# OSPLC2_2_IO3.net
KiCad netlist of a schematic drawn in Altium Designer
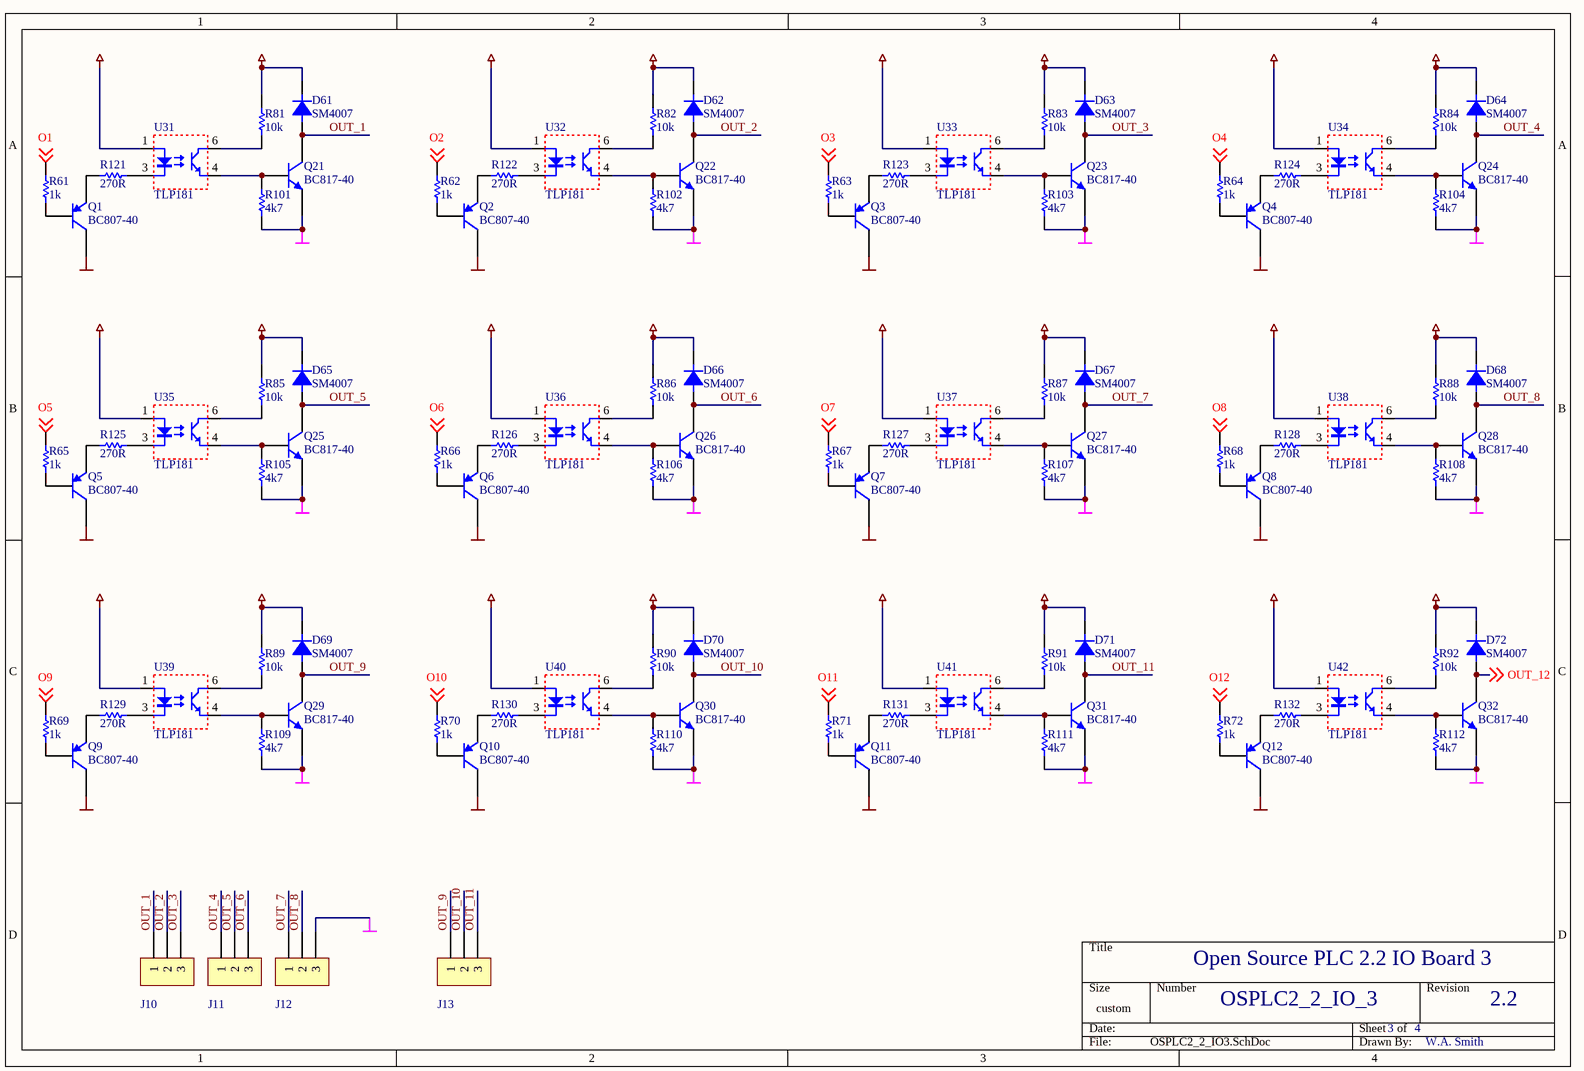
[diagram p0: OSPLC2_2_IO3.SchDoc]

(export (version "E")
  (design (tool "Eeschema 10.0.6"))
  (components
    (comp (ref "D61")
      (value "SM4007")
      (footprint "MELF-2.2x2.5")
      (description "1A, 1000V MELF Rectifier")
      (libsource (lib "ARM_projects") (part "SM4007"))
    )
    (comp (ref "D62")
      (value "SM4007")
      (footprint "MELF-2.2x2.5")
      (description "1A, 1000V MELF Rectifier")
      (libsource (lib "ARM_projects") (part "SM4007"))
    )
    (comp (ref "D63")
      (value "SM4007")
      (footprint "MELF-2.2x2.5")
      (description "1A, 1000V MELF Rectifier")
      (libsource (lib "ARM_projects") (part "SM4007"))
    )
    (comp (ref "D64")
      (value "SM4007")
      (footprint "MELF-2.2x2.5")
      (description "1A, 1000V MELF Rectifier")
      (libsource (lib "ARM_projects") (part "SM4007"))
    )
    (comp (ref "D65")
      (value "SM4007")
      (footprint "MELF-2.2x2.5")
      (description "1A, 1000V MELF Rectifier")
      (libsource (lib "ARM_projects") (part "SM4007"))
    )
    (comp (ref "D66")
      (value "SM4007")
      (footprint "MELF-2.2x2.5")
      (description "1A, 1000V MELF Rectifier")
      (libsource (lib "ARM_projects") (part "SM4007"))
    )
    (comp (ref "D67")
      (value "SM4007")
      (footprint "MELF-2.2x2.5")
      (description "1A, 1000V MELF Rectifier")
      (libsource (lib "ARM_projects") (part "SM4007"))
    )
    (comp (ref "D68")
      (value "SM4007")
      (footprint "MELF-2.2x2.5")
      (description "1A, 1000V MELF Rectifier")
      (libsource (lib "ARM_projects") (part "SM4007"))
    )
    (comp (ref "D69")
      (value "SM4007")
      (footprint "MELF-2.2x2.5")
      (description "1A, 1000V MELF Rectifier")
      (libsource (lib "ARM_projects") (part "SM4007"))
    )
    (comp (ref "D70")
      (value "SM4007")
      (footprint "MELF-2.2x2.5")
      (description "1A, 1000V MELF Rectifier")
      (libsource (lib "ARM_projects") (part "SM4007"))
    )
    (comp (ref "D71")
      (value "SM4007")
      (footprint "MELF-2.2x2.5")
      (description "1A, 1000V MELF Rectifier")
      (libsource (lib "ARM_projects") (part "SM4007"))
    )
    (comp (ref "D72")
      (value "SM4007")
      (footprint "MELF-2.2x2.5")
      (description "1A, 1000V MELF Rectifier")
      (libsource (lib "ARM_projects") (part "SM4007"))
    )
    (comp (ref "J10")
      (value "PCB TERMINAL")
      (footprint "TERMINAL_3WAY_5MM")
      (description "5mm spaced PCB terminal, 3 pole")
      (libsource (lib "ARM_projects") (part "TERMINAL_3WAY_5MM"))
    )
    (comp (ref "J11")
      (value "PCB TERMINAL")
      (footprint "TERMINAL_3WAY_5MM")
      (description "5mm spaced PCB terminal, 3 pole")
      (libsource (lib "ARM_projects") (part "TERMINAL_3WAY_5MM"))
    )
    (comp (ref "J12")
      (value "PCB TERMINAL")
      (footprint "TERMINAL_3WAY_5MM")
      (description "5mm spaced PCB terminal, 3 pole")
      (libsource (lib "ARM_projects") (part "TERMINAL_3WAY_5MM"))
    )
    (comp (ref "J13")
      (value "PCB TERMINAL")
      (footprint "TERMINAL_3WAY_5MM")
      (description "5mm spaced PCB terminal, 3 pole")
      (libsource (lib "ARM_projects") (part "TERMINAL_3WAY_5MM"))
    )
    (comp (ref "Q1")
      (value "BC807-40")
      (footprint "SO-G3/Y1")
      (description "PNP General Purpose Amplifier")
      (fields
        (field (name "MANUFACTURER") "Fairchild Semiconductor")
        (field (name "PUBLISHER") "Altium Limited")
      )
      (libsource (lib "FSC Discrete BJT") (part "BC807-40"))
    )
    (comp (ref "Q2")
      (value "BC807-40")
      (footprint "SO-G3/Y1")
      (description "PNP General Purpose Amplifier")
      (fields
        (field (name "MANUFACTURER") "Fairchild Semiconductor")
        (field (name "PUBLISHER") "Altium Limited")
      )
      (libsource (lib "FSC Discrete BJT") (part "BC807-40"))
    )
    (comp (ref "Q3")
      (value "BC807-40")
      (footprint "SO-G3/Y1")
      (description "PNP General Purpose Amplifier")
      (fields
        (field (name "MANUFACTURER") "Fairchild Semiconductor")
        (field (name "PUBLISHER") "Altium Limited")
      )
      (libsource (lib "FSC Discrete BJT") (part "BC807-40"))
    )
    (comp (ref "Q4")
      (value "BC807-40")
      (footprint "SO-G3/Y1")
      (description "PNP General Purpose Amplifier")
      (fields
        (field (name "MANUFACTURER") "Fairchild Semiconductor")
        (field (name "PUBLISHER") "Altium Limited")
      )
      (libsource (lib "FSC Discrete BJT") (part "BC807-40"))
    )
    (comp (ref "Q5")
      (value "BC807-40")
      (footprint "SO-G3/Y1")
      (description "PNP General Purpose Amplifier")
      (fields
        (field (name "MANUFACTURER") "Fairchild Semiconductor")
        (field (name "PUBLISHER") "Altium Limited")
      )
      (libsource (lib "FSC Discrete BJT") (part "BC807-40"))
    )
    (comp (ref "Q6")
      (value "BC807-40")
      (footprint "SO-G3/Y1")
      (description "PNP General Purpose Amplifier")
      (fields
        (field (name "MANUFACTURER") "Fairchild Semiconductor")
        (field (name "PUBLISHER") "Altium Limited")
      )
      (libsource (lib "FSC Discrete BJT") (part "BC807-40"))
    )
    (comp (ref "Q7")
      (value "BC807-40")
      (footprint "SO-G3/Y1")
      (description "PNP General Purpose Amplifier")
      (fields
        (field (name "MANUFACTURER") "Fairchild Semiconductor")
        (field (name "PUBLISHER") "Altium Limited")
      )
      (libsource (lib "FSC Discrete BJT") (part "BC807-40"))
    )
    (comp (ref "Q8")
      (value "BC807-40")
      (footprint "SO-G3/Y1")
      (description "PNP General Purpose Amplifier")
      (fields
        (field (name "MANUFACTURER") "Fairchild Semiconductor")
        (field (name "PUBLISHER") "Altium Limited")
      )
      (libsource (lib "FSC Discrete BJT") (part "BC807-40"))
    )
    (comp (ref "Q9")
      (value "BC807-40")
      (footprint "SO-G3/Y1")
      (description "PNP General Purpose Amplifier")
      (fields
        (field (name "MANUFACTURER") "Fairchild Semiconductor")
        (field (name "PUBLISHER") "Altium Limited")
      )
      (libsource (lib "FSC Discrete BJT") (part "BC807-40"))
    )
    (comp (ref "Q10")
      (value "BC807-40")
      (footprint "SO-G3/Y1")
      (description "PNP General Purpose Amplifier")
      (fields
        (field (name "MANUFACTURER") "Fairchild Semiconductor")
        (field (name "PUBLISHER") "Altium Limited")
      )
      (libsource (lib "FSC Discrete BJT") (part "BC807-40"))
    )
    (comp (ref "Q11")
      (value "BC807-40")
      (footprint "SO-G3/Y1")
      (description "PNP General Purpose Amplifier")
      (fields
        (field (name "MANUFACTURER") "Fairchild Semiconductor")
        (field (name "PUBLISHER") "Altium Limited")
      )
      (libsource (lib "FSC Discrete BJT") (part "BC807-40"))
    )
    (comp (ref "Q12")
      (value "BC807-40")
      (footprint "SO-G3/Y1")
      (description "PNP General Purpose Amplifier")
      (fields
        (field (name "MANUFACTURER") "Fairchild Semiconductor")
        (field (name "PUBLISHER") "Altium Limited")
      )
      (libsource (lib "FSC Discrete BJT") (part "BC807-40"))
    )
    (comp (ref "Q21")
      (value "BC817-40")
      (footprint "SO-G3/Y1")
      (description "NPN General Purpose Amplifier")
      (fields
        (field (name "MANUFACTURER") "Fairchild Semiconductor")
        (field (name "PUBLISHER") "Altium Limited")
      )
      (libsource (lib "FSC Discrete BJT") (part "BC817-40"))
    )
    (comp (ref "Q22")
      (value "BC817-40")
      (footprint "SO-G3/Y1")
      (description "NPN General Purpose Amplifier")
      (fields
        (field (name "MANUFACTURER") "Fairchild Semiconductor")
        (field (name "PUBLISHER") "Altium Limited")
      )
      (libsource (lib "FSC Discrete BJT") (part "BC817-40"))
    )
    (comp (ref "Q23")
      (value "BC817-40")
      (footprint "SO-G3/Y1")
      (description "NPN General Purpose Amplifier")
      (fields
        (field (name "MANUFACTURER") "Fairchild Semiconductor")
        (field (name "PUBLISHER") "Altium Limited")
      )
      (libsource (lib "FSC Discrete BJT") (part "BC817-40"))
    )
    (comp (ref "Q24")
      (value "BC817-40")
      (footprint "SO-G3/Y1")
      (description "NPN General Purpose Amplifier")
      (fields
        (field (name "MANUFACTURER") "Fairchild Semiconductor")
        (field (name "PUBLISHER") "Altium Limited")
      )
      (libsource (lib "FSC Discrete BJT") (part "BC817-40"))
    )
    (comp (ref "Q25")
      (value "BC817-40")
      (footprint "SO-G3/Y1")
      (description "NPN General Purpose Amplifier")
      (fields
        (field (name "MANUFACTURER") "Fairchild Semiconductor")
        (field (name "PUBLISHER") "Altium Limited")
      )
      (libsource (lib "FSC Discrete BJT") (part "BC817-40"))
    )
    (comp (ref "Q26")
      (value "BC817-40")
      (footprint "SO-G3/Y1")
      (description "NPN General Purpose Amplifier")
      (fields
        (field (name "MANUFACTURER") "Fairchild Semiconductor")
        (field (name "PUBLISHER") "Altium Limited")
      )
      (libsource (lib "FSC Discrete BJT") (part "BC817-40"))
    )
    (comp (ref "Q27")
      (value "BC817-40")
      (footprint "SO-G3/Y1")
      (description "NPN General Purpose Amplifier")
      (fields
        (field (name "MANUFACTURER") "Fairchild Semiconductor")
        (field (name "PUBLISHER") "Altium Limited")
      )
      (libsource (lib "FSC Discrete BJT") (part "BC817-40"))
    )
    (comp (ref "Q28")
      (value "BC817-40")
      (footprint "SO-G3/Y1")
      (description "NPN General Purpose Amplifier")
      (fields
        (field (name "MANUFACTURER") "Fairchild Semiconductor")
        (field (name "PUBLISHER") "Altium Limited")
      )
      (libsource (lib "FSC Discrete BJT") (part "BC817-40"))
    )
    (comp (ref "Q29")
      (value "BC817-40")
      (footprint "SO-G3/Y1")
      (description "NPN General Purpose Amplifier")
      (fields
        (field (name "MANUFACTURER") "Fairchild Semiconductor")
        (field (name "PUBLISHER") "Altium Limited")
      )
      (libsource (lib "FSC Discrete BJT") (part "BC817-40"))
    )
    (comp (ref "Q30")
      (value "BC817-40")
      (footprint "SO-G3/Y1")
      (description "NPN General Purpose Amplifier")
      (fields
        (field (name "MANUFACTURER") "Fairchild Semiconductor")
        (field (name "PUBLISHER") "Altium Limited")
      )
      (libsource (lib "FSC Discrete BJT") (part "BC817-40"))
    )
    (comp (ref "Q31")
      (value "BC817-40")
      (footprint "SO-G3/Y1")
      (description "NPN General Purpose Amplifier")
      (fields
        (field (name "MANUFACTURER") "Fairchild Semiconductor")
        (field (name "PUBLISHER") "Altium Limited")
      )
      (libsource (lib "FSC Discrete BJT") (part "BC817-40"))
    )
    (comp (ref "Q32")
      (value "BC817-40")
      (footprint "SO-G3/Y1")
      (description "NPN General Purpose Amplifier")
      (fields
        (field (name "MANUFACTURER") "Fairchild Semiconductor")
        (field (name "PUBLISHER") "Altium Limited")
      )
      (libsource (lib "FSC Discrete BJT") (part "BC817-40"))
    )
    (comp (ref "R61")
      (value "0805")
      (footprint "0805")
      (description "0805 footprint resistor")
      (fields (field (name "ALTIUM_VALUE") "1k"))
      (libsource (lib "Integrated Comp_lib") (part "RES_0805"))
    )
    (comp (ref "R62")
      (value "0805")
      (footprint "0805")
      (description "0805 footprint resistor")
      (fields (field (name "ALTIUM_VALUE") "1k"))
      (libsource (lib "Integrated Comp_lib") (part "RES_0805"))
    )
    (comp (ref "R63")
      (value "0805")
      (footprint "0805")
      (description "0805 footprint resistor")
      (fields (field (name "ALTIUM_VALUE") "1k"))
      (libsource (lib "Integrated Comp_lib") (part "RES_0805"))
    )
    (comp (ref "R64")
      (value "0805")
      (footprint "0805")
      (description "0805 footprint resistor")
      (fields (field (name "ALTIUM_VALUE") "1k"))
      (libsource (lib "Integrated Comp_lib") (part "RES_0805"))
    )
    (comp (ref "R65")
      (value "0805")
      (footprint "0805")
      (description "0805 footprint resistor")
      (fields (field (name "ALTIUM_VALUE") "1k"))
      (libsource (lib "Integrated Comp_lib") (part "RES_0805"))
    )
    (comp (ref "R66")
      (value "0805")
      (footprint "0805")
      (description "0805 footprint resistor")
      (fields (field (name "ALTIUM_VALUE") "1k"))
      (libsource (lib "Integrated Comp_lib") (part "RES_0805"))
    )
    (comp (ref "R67")
      (value "0805")
      (footprint "0805")
      (description "0805 footprint resistor")
      (fields (field (name "ALTIUM_VALUE") "1k"))
      (libsource (lib "Integrated Comp_lib") (part "RES_0805"))
    )
    (comp (ref "R68")
      (value "0805")
      (footprint "0805")
      (description "0805 footprint resistor")
      (fields (field (name "ALTIUM_VALUE") "1k"))
      (libsource (lib "Integrated Comp_lib") (part "RES_0805"))
    )
    (comp (ref "R69")
      (value "0805")
      (footprint "0805")
      (description "0805 footprint resistor")
      (fields (field (name "ALTIUM_VALUE") "1k"))
      (libsource (lib "Integrated Comp_lib") (part "RES_0805"))
    )
    (comp (ref "R70")
      (value "0805")
      (footprint "0805")
      (description "0805 footprint resistor")
      (fields (field (name "ALTIUM_VALUE") "1k"))
      (libsource (lib "Integrated Comp_lib") (part "RES_0805"))
    )
    (comp (ref "R71")
      (value "0805")
      (footprint "0805")
      (description "0805 footprint resistor")
      (fields (field (name "ALTIUM_VALUE") "1k"))
      (libsource (lib "Integrated Comp_lib") (part "RES_0805"))
    )
    (comp (ref "R72")
      (value "0805")
      (footprint "0805")
      (description "0805 footprint resistor")
      (fields (field (name "ALTIUM_VALUE") "1k"))
      (libsource (lib "Integrated Comp_lib") (part "RES_0805"))
    )
    (comp (ref "R81")
      (value "0805")
      (footprint "0805")
      (description "0805 footprint resistor")
      (fields (field (name "ALTIUM_VALUE") "10k"))
      (libsource (lib "Integrated Comp_lib") (part "RES_0805"))
    )
    (comp (ref "R82")
      (value "0805")
      (footprint "0805")
      (description "0805 footprint resistor")
      (fields (field (name "ALTIUM_VALUE") "10k"))
      (libsource (lib "Integrated Comp_lib") (part "RES_0805"))
    )
    (comp (ref "R83")
      (value "0805")
      (footprint "0805")
      (description "0805 footprint resistor")
      (fields (field (name "ALTIUM_VALUE") "10k"))
      (libsource (lib "Integrated Comp_lib") (part "RES_0805"))
    )
    (comp (ref "R84")
      (value "0805")
      (footprint "0805")
      (description "0805 footprint resistor")
      (fields (field (name "ALTIUM_VALUE") "10k"))
      (libsource (lib "Integrated Comp_lib") (part "RES_0805"))
    )
    (comp (ref "R85")
      (value "0805")
      (footprint "0805")
      (description "0805 footprint resistor")
      (fields (field (name "ALTIUM_VALUE") "10k"))
      (libsource (lib "Integrated Comp_lib") (part "RES_0805"))
    )
    (comp (ref "R86")
      (value "0805")
      (footprint "0805")
      (description "0805 footprint resistor")
      (fields (field (name "ALTIUM_VALUE") "10k"))
      (libsource (lib "Integrated Comp_lib") (part "RES_0805"))
    )
    (comp (ref "R87")
      (value "0805")
      (footprint "0805")
      (description "0805 footprint resistor")
      (fields (field (name "ALTIUM_VALUE") "10k"))
      (libsource (lib "Integrated Comp_lib") (part "RES_0805"))
    )
    (comp (ref "R88")
      (value "0805")
      (footprint "0805")
      (description "0805 footprint resistor")
      (fields (field (name "ALTIUM_VALUE") "10k"))
      (libsource (lib "Integrated Comp_lib") (part "RES_0805"))
    )
    (comp (ref "R89")
      (value "0805")
      (footprint "0805")
      (description "0805 footprint resistor")
      (fields (field (name "ALTIUM_VALUE") "10k"))
      (libsource (lib "Integrated Comp_lib") (part "RES_0805"))
    )
    (comp (ref "R90")
      (value "0805")
      (footprint "0805")
      (description "0805 footprint resistor")
      (fields (field (name "ALTIUM_VALUE") "10k"))
      (libsource (lib "Integrated Comp_lib") (part "RES_0805"))
    )
    (comp (ref "R91")
      (value "0805")
      (footprint "0805")
      (description "0805 footprint resistor")
      (fields (field (name "ALTIUM_VALUE") "10k"))
      (libsource (lib "Integrated Comp_lib") (part "RES_0805"))
    )
    (comp (ref "R92")
      (value "0805")
      (footprint "0805")
      (description "0805 footprint resistor")
      (fields (field (name "ALTIUM_VALUE") "10k"))
      (libsource (lib "Integrated Comp_lib") (part "RES_0805"))
    )
    (comp (ref "R101")
      (value "0805")
      (footprint "0805")
      (description "0805 footprint resistor")
      (fields (field (name "ALTIUM_VALUE") "4k7"))
      (libsource (lib "Integrated Comp_lib") (part "RES_0805"))
    )
    (comp (ref "R102")
      (value "0805")
      (footprint "0805")
      (description "0805 footprint resistor")
      (fields (field (name "ALTIUM_VALUE") "4k7"))
      (libsource (lib "Integrated Comp_lib") (part "RES_0805"))
    )
    (comp (ref "R103")
      (value "0805")
      (footprint "0805")
      (description "0805 footprint resistor")
      (fields (field (name "ALTIUM_VALUE") "4k7"))
      (libsource (lib "Integrated Comp_lib") (part "RES_0805"))
    )
    (comp (ref "R104")
      (value "0805")
      (footprint "0805")
      (description "0805 footprint resistor")
      (fields (field (name "ALTIUM_VALUE") "4k7"))
      (libsource (lib "Integrated Comp_lib") (part "RES_0805"))
    )
    (comp (ref "R105")
      (value "0805")
      (footprint "0805")
      (description "0805 footprint resistor")
      (fields (field (name "ALTIUM_VALUE") "4k7"))
      (libsource (lib "Integrated Comp_lib") (part "RES_0805"))
    )
    (comp (ref "R106")
      (value "0805")
      (footprint "0805")
      (description "0805 footprint resistor")
      (fields (field (name "ALTIUM_VALUE") "4k7"))
      (libsource (lib "Integrated Comp_lib") (part "RES_0805"))
    )
    (comp (ref "R107")
      (value "0805")
      (footprint "0805")
      (description "0805 footprint resistor")
      (fields (field (name "ALTIUM_VALUE") "4k7"))
      (libsource (lib "Integrated Comp_lib") (part "RES_0805"))
    )
    (comp (ref "R108")
      (value "0805")
      (footprint "0805")
      (description "0805 footprint resistor")
      (fields (field (name "ALTIUM_VALUE") "4k7"))
      (libsource (lib "Integrated Comp_lib") (part "RES_0805"))
    )
    (comp (ref "R109")
      (value "0805")
      (footprint "0805")
      (description "0805 footprint resistor")
      (fields (field (name "ALTIUM_VALUE") "4k7"))
      (libsource (lib "Integrated Comp_lib") (part "RES_0805"))
    )
    (comp (ref "R110")
      (value "0805")
      (footprint "0805")
      (description "0805 footprint resistor")
      (fields (field (name "ALTIUM_VALUE") "4k7"))
      (libsource (lib "Integrated Comp_lib") (part "RES_0805"))
    )
    (comp (ref "R111")
      (value "0805")
      (footprint "0805")
      (description "0805 footprint resistor")
      (fields (field (name "ALTIUM_VALUE") "4k7"))
      (libsource (lib "Integrated Comp_lib") (part "RES_0805"))
    )
    (comp (ref "R112")
      (value "0805")
      (footprint "0805")
      (description "0805 footprint resistor")
      (fields (field (name "ALTIUM_VALUE") "4k7"))
      (libsource (lib "Integrated Comp_lib") (part "RES_0805"))
    )
    (comp (ref "R121")
      (value "0805")
      (footprint "0805")
      (description "0805 footprint resistor")
      (fields (field (name "ALTIUM_VALUE") "270R"))
      (libsource (lib "Integrated Comp_lib") (part "RES_0805"))
    )
    (comp (ref "R122")
      (value "0805")
      (footprint "0805")
      (description "0805 footprint resistor")
      (fields (field (name "ALTIUM_VALUE") "270R"))
      (libsource (lib "Integrated Comp_lib") (part "RES_0805"))
    )
    (comp (ref "R123")
      (value "0805")
      (footprint "0805")
      (description "0805 footprint resistor")
      (fields (field (name "ALTIUM_VALUE") "270R"))
      (libsource (lib "Integrated Comp_lib") (part "RES_0805"))
    )
    (comp (ref "R124")
      (value "0805")
      (footprint "0805")
      (description "0805 footprint resistor")
      (fields (field (name "ALTIUM_VALUE") "270R"))
      (libsource (lib "Integrated Comp_lib") (part "RES_0805"))
    )
    (comp (ref "R125")
      (value "0805")
      (footprint "0805")
      (description "0805 footprint resistor")
      (fields (field (name "ALTIUM_VALUE") "270R"))
      (libsource (lib "Integrated Comp_lib") (part "RES_0805"))
    )
    (comp (ref "R126")
      (value "0805")
      (footprint "0805")
      (description "0805 footprint resistor")
      (fields (field (name "ALTIUM_VALUE") "270R"))
      (libsource (lib "Integrated Comp_lib") (part "RES_0805"))
    )
    (comp (ref "R127")
      (value "0805")
      (footprint "0805")
      (description "0805 footprint resistor")
      (fields (field (name "ALTIUM_VALUE") "270R"))
      (libsource (lib "Integrated Comp_lib") (part "RES_0805"))
    )
    (comp (ref "R128")
      (value "0805")
      (footprint "0805")
      (description "0805 footprint resistor")
      (fields (field (name "ALTIUM_VALUE") "270R"))
      (libsource (lib "Integrated Comp_lib") (part "RES_0805"))
    )
    (comp (ref "R129")
      (value "0805")
      (footprint "0805")
      (description "0805 footprint resistor")
      (fields (field (name "ALTIUM_VALUE") "270R"))
      (libsource (lib "Integrated Comp_lib") (part "RES_0805"))
    )
    (comp (ref "R130")
      (value "0805")
      (footprint "0805")
      (description "0805 footprint resistor")
      (fields (field (name "ALTIUM_VALUE") "270R"))
      (libsource (lib "Integrated Comp_lib") (part "RES_0805"))
    )
    (comp (ref "R131")
      (value "0805")
      (footprint "0805")
      (description "0805 footprint resistor")
      (fields (field (name "ALTIUM_VALUE") "270R"))
      (libsource (lib "Integrated Comp_lib") (part "RES_0805"))
    )
    (comp (ref "R132")
      (value "0805")
      (footprint "0805")
      (description "0805 footprint resistor")
      (fields (field (name "ALTIUM_VALUE") "270R"))
      (libsource (lib "Integrated Comp_lib") (part "RES_0805"))
    )
    (comp (ref "U31")
      (value "TLP181")
      (footprint "SOP4_2.54")
      (description "Toshiba Photocoupler")
      (libsource (lib "Integrated Comp_lib") (part "TLP181"))
    )
    (comp (ref "U32")
      (value "TLP181")
      (footprint "SOP4_2.54")
      (description "Toshiba Photocoupler")
      (libsource (lib "Integrated Comp_lib") (part "TLP181"))
    )
    (comp (ref "U33")
      (value "TLP181")
      (footprint "SOP4_2.54")
      (description "Toshiba Photocoupler")
      (libsource (lib "Integrated Comp_lib") (part "TLP181"))
    )
    (comp (ref "U34")
      (value "TLP181")
      (footprint "SOP4_2.54")
      (description "Toshiba Photocoupler")
      (libsource (lib "Integrated Comp_lib") (part "TLP181"))
    )
    (comp (ref "U35")
      (value "TLP181")
      (footprint "SOP4_2.54")
      (description "Toshiba Photocoupler")
      (libsource (lib "Integrated Comp_lib") (part "TLP181"))
    )
    (comp (ref "U36")
      (value "TLP181")
      (footprint "SOP4_2.54")
      (description "Toshiba Photocoupler")
      (libsource (lib "Integrated Comp_lib") (part "TLP181"))
    )
    (comp (ref "U37")
      (value "TLP181")
      (footprint "SOP4_2.54")
      (description "Toshiba Photocoupler")
      (libsource (lib "Integrated Comp_lib") (part "TLP181"))
    )
    (comp (ref "U38")
      (value "TLP181")
      (footprint "SOP4_2.54")
      (description "Toshiba Photocoupler")
      (libsource (lib "Integrated Comp_lib") (part "TLP181"))
    )
    (comp (ref "U39")
      (value "TLP181")
      (footprint "SOP4_2.54")
      (description "Toshiba Photocoupler")
      (libsource (lib "Integrated Comp_lib") (part "TLP181"))
    )
    (comp (ref "U40")
      (value "TLP181")
      (footprint "SOP4_2.54")
      (description "Toshiba Photocoupler")
      (libsource (lib "Integrated Comp_lib") (part "TLP181"))
    )
    (comp (ref "U41")
      (value "TLP181")
      (footprint "SOP4_2.54")
      (description "Toshiba Photocoupler")
      (libsource (lib "Integrated Comp_lib") (part "TLP181"))
    )
    (comp (ref "U42")
      (value "TLP181")
      (footprint "SOP4_2.54")
      (description "Toshiba Photocoupler")
      (libsource (lib "Integrated Comp_lib") (part "TLP181"))
    )
  )
  (nets
    (net (code "1") (name "/OUT_1") (class "Default")
      (node (ref "D61") (pin "1") (pinfunction "A_1") (pintype "passive"))
      (node (ref "J10") (pin "1") (pinfunction "1_1") (pintype "passive"))
      (node (ref "Q21") (pin "3") (pinfunction "C_3") (pintype "passive"))
    )
    (net (code "2") (name "/OUT_2") (class "Default")
      (node (ref "D62") (pin "1") (pinfunction "A_1") (pintype "passive"))
      (node (ref "J10") (pin "2") (pinfunction "2_2") (pintype "passive"))
      (node (ref "Q22") (pin "3") (pinfunction "C_3") (pintype "passive"))
    )
    (net (code "3") (name "/OUT_3") (class "Default")
      (node (ref "D63") (pin "1") (pinfunction "A_1") (pintype "passive"))
      (node (ref "J10") (pin "3") (pinfunction "3_3") (pintype "passive"))
      (node (ref "Q23") (pin "3") (pinfunction "C_3") (pintype "passive"))
    )
    (net (code "4") (name "/OUT_4") (class "Default")
      (node (ref "D64") (pin "1") (pinfunction "A_1") (pintype "passive"))
      (node (ref "J11") (pin "1") (pinfunction "1_1") (pintype "passive"))
      (node (ref "Q24") (pin "3") (pinfunction "C_3") (pintype "passive"))
    )
    (net (code "5") (name "/OUT_5") (class "Default")
      (node (ref "D65") (pin "1") (pinfunction "A_1") (pintype "passive"))
      (node (ref "J11") (pin "2") (pinfunction "2_2") (pintype "passive"))
      (node (ref "Q25") (pin "3") (pinfunction "C_3") (pintype "passive"))
    )
    (net (code "6") (name "/OUT_6") (class "Default")
      (node (ref "D66") (pin "1") (pinfunction "A_1") (pintype "passive"))
      (node (ref "J11") (pin "3") (pinfunction "3_3") (pintype "passive"))
      (node (ref "Q26") (pin "3") (pinfunction "C_3") (pintype "passive"))
    )
    (net (code "7") (name "/OUT_7") (class "Default")
      (node (ref "D67") (pin "1") (pinfunction "A_1") (pintype "passive"))
      (node (ref "J12") (pin "1") (pinfunction "1_1") (pintype "passive"))
      (node (ref "Q27") (pin "3") (pinfunction "C_3") (pintype "passive"))
    )
    (net (code "8") (name "/OUT_8") (class "Default")
      (node (ref "D68") (pin "1") (pinfunction "A_1") (pintype "passive"))
      (node (ref "J12") (pin "2") (pinfunction "2_2") (pintype "passive"))
      (node (ref "Q28") (pin "3") (pinfunction "C_3") (pintype "passive"))
    )
    (net (code "9") (name "/OUT_9") (class "Default")
      (node (ref "D69") (pin "1") (pinfunction "A_1") (pintype "passive"))
      (node (ref "J13") (pin "1") (pinfunction "1_1") (pintype "passive"))
      (node (ref "Q29") (pin "3") (pinfunction "C_3") (pintype "passive"))
    )
    (net (code "10") (name "/OUT_10") (class "Default")
      (node (ref "D70") (pin "1") (pinfunction "A_1") (pintype "passive"))
      (node (ref "J13") (pin "2") (pinfunction "2_2") (pintype "passive"))
      (node (ref "Q30") (pin "3") (pinfunction "C_3") (pintype "passive"))
    )
    (net (code "11") (name "/OUT_11") (class "Default")
      (node (ref "D71") (pin "1") (pinfunction "A_1") (pintype "passive"))
      (node (ref "J13") (pin "3") (pinfunction "3_3") (pintype "passive"))
      (node (ref "Q31") (pin "3") (pinfunction "C_3") (pintype "passive"))
    )
    (net (code "12") (name "GND") (class "Default")
      (node (ref "Q1") (pin "3") (pinfunction "C_3") (pintype "passive"))
      (node (ref "Q10") (pin "3") (pinfunction "C_3") (pintype "passive"))
      (node (ref "Q11") (pin "3") (pinfunction "C_3") (pintype "passive"))
      (node (ref "Q12") (pin "3") (pinfunction "C_3") (pintype "passive"))
      (node (ref "Q2") (pin "3") (pinfunction "C_3") (pintype "passive"))
      (node (ref "Q3") (pin "3") (pinfunction "C_3") (pintype "passive"))
      (node (ref "Q4") (pin "3") (pinfunction "C_3") (pintype "passive"))
      (node (ref "Q5") (pin "3") (pinfunction "C_3") (pintype "passive"))
      (node (ref "Q6") (pin "3") (pinfunction "C_3") (pintype "passive"))
      (node (ref "Q7") (pin "3") (pinfunction "C_3") (pintype "passive"))
      (node (ref "Q8") (pin "3") (pinfunction "C_3") (pintype "passive"))
      (node (ref "Q9") (pin "3") (pinfunction "C_3") (pintype "passive"))
    )
    (net (code "13") (name "Net-(Q1-B)") (class "Default")
      (node (ref "Q1") (pin "1") (pinfunction "B_1") (pintype "passive"))
      (node (ref "R61") (pin "1") (pinfunction "1_1") (pintype "passive"))
    )
    (net (code "14") (name "Net-(Q1-E)") (class "Default")
      (node (ref "Q1") (pin "2") (pinfunction "E_2") (pintype "passive"))
      (node (ref "R121") (pin "1") (pinfunction "1_1") (pintype "passive"))
    )
    (net (code "15") (name "Net-(Q2-B)") (class "Default")
      (node (ref "Q2") (pin "1") (pinfunction "B_1") (pintype "passive"))
      (node (ref "R62") (pin "1") (pinfunction "1_1") (pintype "passive"))
    )
    (net (code "16") (name "Net-(Q2-E)") (class "Default")
      (node (ref "Q2") (pin "2") (pinfunction "E_2") (pintype "passive"))
      (node (ref "R122") (pin "1") (pinfunction "1_1") (pintype "passive"))
    )
    (net (code "17") (name "Net-(Q3-B)") (class "Default")
      (node (ref "Q3") (pin "1") (pinfunction "B_1") (pintype "passive"))
      (node (ref "R63") (pin "1") (pinfunction "1_1") (pintype "passive"))
    )
    (net (code "18") (name "Net-(Q3-E)") (class "Default")
      (node (ref "Q3") (pin "2") (pinfunction "E_2") (pintype "passive"))
      (node (ref "R123") (pin "1") (pinfunction "1_1") (pintype "passive"))
    )
    (net (code "19") (name "Net-(Q4-B)") (class "Default")
      (node (ref "Q4") (pin "1") (pinfunction "B_1") (pintype "passive"))
      (node (ref "R64") (pin "1") (pinfunction "1_1") (pintype "passive"))
    )
    (net (code "20") (name "Net-(Q4-E)") (class "Default")
      (node (ref "Q4") (pin "2") (pinfunction "E_2") (pintype "passive"))
      (node (ref "R124") (pin "1") (pinfunction "1_1") (pintype "passive"))
    )
    (net (code "21") (name "Net-(Q5-B)") (class "Default")
      (node (ref "Q5") (pin "1") (pinfunction "B_1") (pintype "passive"))
      (node (ref "R65") (pin "1") (pinfunction "1_1") (pintype "passive"))
    )
    (net (code "22") (name "Net-(Q5-E)") (class "Default")
      (node (ref "Q5") (pin "2") (pinfunction "E_2") (pintype "passive"))
      (node (ref "R125") (pin "1") (pinfunction "1_1") (pintype "passive"))
    )
    (net (code "23") (name "Net-(Q6-B)") (class "Default")
      (node (ref "Q6") (pin "1") (pinfunction "B_1") (pintype "passive"))
      (node (ref "R66") (pin "1") (pinfunction "1_1") (pintype "passive"))
    )
    (net (code "24") (name "Net-(Q6-E)") (class "Default")
      (node (ref "Q6") (pin "2") (pinfunction "E_2") (pintype "passive"))
      (node (ref "R126") (pin "1") (pinfunction "1_1") (pintype "passive"))
    )
    (net (code "25") (name "Net-(Q7-B)") (class "Default")
      (node (ref "Q7") (pin "1") (pinfunction "B_1") (pintype "passive"))
      (node (ref "R67") (pin "1") (pinfunction "1_1") (pintype "passive"))
    )
    (net (code "26") (name "Net-(Q7-E)") (class "Default")
      (node (ref "Q7") (pin "2") (pinfunction "E_2") (pintype "passive"))
      (node (ref "R127") (pin "1") (pinfunction "1_1") (pintype "passive"))
    )
    (net (code "27") (name "Net-(Q8-B)") (class "Default")
      (node (ref "Q8") (pin "1") (pinfunction "B_1") (pintype "passive"))
      (node (ref "R68") (pin "1") (pinfunction "1_1") (pintype "passive"))
    )
    (net (code "28") (name "Net-(Q8-E)") (class "Default")
      (node (ref "Q8") (pin "2") (pinfunction "E_2") (pintype "passive"))
      (node (ref "R128") (pin "1") (pinfunction "1_1") (pintype "passive"))
    )
    (net (code "29") (name "Net-(Q9-B)") (class "Default")
      (node (ref "Q9") (pin "1") (pinfunction "B_1") (pintype "passive"))
      (node (ref "R69") (pin "1") (pinfunction "1_1") (pintype "passive"))
    )
    (net (code "30") (name "Net-(Q9-E)") (class "Default")
      (node (ref "Q9") (pin "2") (pinfunction "E_2") (pintype "passive"))
      (node (ref "R129") (pin "1") (pinfunction "1_1") (pintype "passive"))
    )
    (net (code "31") (name "Net-(Q10-B)") (class "Default")
      (node (ref "Q10") (pin "1") (pinfunction "B_1") (pintype "passive"))
      (node (ref "R70") (pin "1") (pinfunction "1_1") (pintype "passive"))
    )
    (net (code "32") (name "Net-(Q10-E)") (class "Default")
      (node (ref "Q10") (pin "2") (pinfunction "E_2") (pintype "passive"))
      (node (ref "R130") (pin "1") (pinfunction "1_1") (pintype "passive"))
    )
    (net (code "33") (name "Net-(Q11-B)") (class "Default")
      (node (ref "Q11") (pin "1") (pinfunction "B_1") (pintype "passive"))
      (node (ref "R71") (pin "1") (pinfunction "1_1") (pintype "passive"))
    )
    (net (code "34") (name "Net-(Q11-E)") (class "Default")
      (node (ref "Q11") (pin "2") (pinfunction "E_2") (pintype "passive"))
      (node (ref "R131") (pin "1") (pinfunction "1_1") (pintype "passive"))
    )
    (net (code "35") (name "Net-(Q12-B)") (class "Default")
      (node (ref "Q12") (pin "1") (pinfunction "B_1") (pintype "passive"))
      (node (ref "R72") (pin "1") (pinfunction "1_1") (pintype "passive"))
    )
    (net (code "36") (name "Net-(Q12-E)") (class "Default")
      (node (ref "Q12") (pin "2") (pinfunction "E_2") (pintype "passive"))
      (node (ref "R132") (pin "1") (pinfunction "1_1") (pintype "passive"))
    )
    (net (code "37") (name "Net-(Q21-B)") (class "Default")
      (node (ref "Q21") (pin "1") (pinfunction "B_1") (pintype "passive"))
      (node (ref "R101") (pin "2") (pinfunction "2_2") (pintype "passive"))
      (node (ref "U31") (pin "4") (pinfunction "4_4") (pintype "passive"))
    )
    (net (code "38") (name "Net-(Q22-B)") (class "Default")
      (node (ref "Q22") (pin "1") (pinfunction "B_1") (pintype "passive"))
      (node (ref "R102") (pin "2") (pinfunction "2_2") (pintype "passive"))
      (node (ref "U32") (pin "4") (pinfunction "4_4") (pintype "passive"))
    )
    (net (code "39") (name "Net-(Q23-B)") (class "Default")
      (node (ref "Q23") (pin "1") (pinfunction "B_1") (pintype "passive"))
      (node (ref "R103") (pin "2") (pinfunction "2_2") (pintype "passive"))
      (node (ref "U33") (pin "4") (pinfunction "4_4") (pintype "passive"))
    )
    (net (code "40") (name "Net-(Q24-B)") (class "Default")
      (node (ref "Q24") (pin "1") (pinfunction "B_1") (pintype "passive"))
      (node (ref "R104") (pin "2") (pinfunction "2_2") (pintype "passive"))
      (node (ref "U34") (pin "4") (pinfunction "4_4") (pintype "passive"))
    )
    (net (code "41") (name "Net-(Q25-B)") (class "Default")
      (node (ref "Q25") (pin "1") (pinfunction "B_1") (pintype "passive"))
      (node (ref "R105") (pin "2") (pinfunction "2_2") (pintype "passive"))
      (node (ref "U35") (pin "4") (pinfunction "4_4") (pintype "passive"))
    )
    (net (code "42") (name "Net-(Q26-B)") (class "Default")
      (node (ref "Q26") (pin "1") (pinfunction "B_1") (pintype "passive"))
      (node (ref "R106") (pin "2") (pinfunction "2_2") (pintype "passive"))
      (node (ref "U36") (pin "4") (pinfunction "4_4") (pintype "passive"))
    )
    (net (code "43") (name "Net-(Q27-B)") (class "Default")
      (node (ref "Q27") (pin "1") (pinfunction "B_1") (pintype "passive"))
      (node (ref "R107") (pin "2") (pinfunction "2_2") (pintype "passive"))
      (node (ref "U37") (pin "4") (pinfunction "4_4") (pintype "passive"))
    )
    (net (code "44") (name "Net-(Q28-B)") (class "Default")
      (node (ref "Q28") (pin "1") (pinfunction "B_1") (pintype "passive"))
      (node (ref "R108") (pin "2") (pinfunction "2_2") (pintype "passive"))
      (node (ref "U38") (pin "4") (pinfunction "4_4") (pintype "passive"))
    )
    (net (code "45") (name "Net-(Q29-B)") (class "Default")
      (node (ref "Q29") (pin "1") (pinfunction "B_1") (pintype "passive"))
      (node (ref "R109") (pin "2") (pinfunction "2_2") (pintype "passive"))
      (node (ref "U39") (pin "4") (pinfunction "4_4") (pintype "passive"))
    )
    (net (code "46") (name "Net-(Q30-B)") (class "Default")
      (node (ref "Q30") (pin "1") (pinfunction "B_1") (pintype "passive"))
      (node (ref "R110") (pin "2") (pinfunction "2_2") (pintype "passive"))
      (node (ref "U40") (pin "4") (pinfunction "4_4") (pintype "passive"))
    )
    (net (code "47") (name "Net-(Q31-B)") (class "Default")
      (node (ref "Q31") (pin "1") (pinfunction "B_1") (pintype "passive"))
      (node (ref "R111") (pin "2") (pinfunction "2_2") (pintype "passive"))
      (node (ref "U41") (pin "4") (pinfunction "4_4") (pintype "passive"))
    )
    (net (code "48") (name "Net-(Q32-B)") (class "Default")
      (node (ref "Q32") (pin "1") (pinfunction "B_1") (pintype "passive"))
      (node (ref "R112") (pin "2") (pinfunction "2_2") (pintype "passive"))
      (node (ref "U42") (pin "4") (pinfunction "4_4") (pintype "passive"))
    )
    (net (code "49") (name "Net-(R81-Pad1)") (class "Default")
      (node (ref "R81") (pin "1") (pinfunction "1_1") (pintype "passive"))
      (node (ref "U31") (pin "6") (pinfunction "6_6") (pintype "passive"))
    )
    (net (code "50") (name "Net-(R82-Pad1)") (class "Default")
      (node (ref "R82") (pin "1") (pinfunction "1_1") (pintype "passive"))
      (node (ref "U32") (pin "6") (pinfunction "6_6") (pintype "passive"))
    )
    (net (code "51") (name "Net-(R83-Pad1)") (class "Default")
      (node (ref "R83") (pin "1") (pinfunction "1_1") (pintype "passive"))
      (node (ref "U33") (pin "6") (pinfunction "6_6") (pintype "passive"))
    )
    (net (code "52") (name "Net-(R84-Pad1)") (class "Default")
      (node (ref "R84") (pin "1") (pinfunction "1_1") (pintype "passive"))
      (node (ref "U34") (pin "6") (pinfunction "6_6") (pintype "passive"))
    )
    (net (code "53") (name "Net-(R85-Pad1)") (class "Default")
      (node (ref "R85") (pin "1") (pinfunction "1_1") (pintype "passive"))
      (node (ref "U35") (pin "6") (pinfunction "6_6") (pintype "passive"))
    )
    (net (code "54") (name "Net-(R86-Pad1)") (class "Default")
      (node (ref "R86") (pin "1") (pinfunction "1_1") (pintype "passive"))
      (node (ref "U36") (pin "6") (pinfunction "6_6") (pintype "passive"))
    )
    (net (code "55") (name "Net-(R87-Pad1)") (class "Default")
      (node (ref "R87") (pin "1") (pinfunction "1_1") (pintype "passive"))
      (node (ref "U37") (pin "6") (pinfunction "6_6") (pintype "passive"))
    )
    (net (code "56") (name "Net-(R88-Pad1)") (class "Default")
      (node (ref "R88") (pin "1") (pinfunction "1_1") (pintype "passive"))
      (node (ref "U38") (pin "6") (pinfunction "6_6") (pintype "passive"))
    )
    (net (code "57") (name "Net-(R89-Pad1)") (class "Default")
      (node (ref "R89") (pin "1") (pinfunction "1_1") (pintype "passive"))
      (node (ref "U39") (pin "6") (pinfunction "6_6") (pintype "passive"))
    )
    (net (code "58") (name "Net-(R90-Pad1)") (class "Default")
      (node (ref "R90") (pin "1") (pinfunction "1_1") (pintype "passive"))
      (node (ref "U40") (pin "6") (pinfunction "6_6") (pintype "passive"))
    )
    (net (code "59") (name "Net-(R91-Pad1)") (class "Default")
      (node (ref "R91") (pin "1") (pinfunction "1_1") (pintype "passive"))
      (node (ref "U41") (pin "6") (pinfunction "6_6") (pintype "passive"))
    )
    (net (code "60") (name "Net-(R92-Pad1)") (class "Default")
      (node (ref "R92") (pin "1") (pinfunction "1_1") (pintype "passive"))
      (node (ref "U42") (pin "6") (pinfunction "6_6") (pintype "passive"))
    )
    (net (code "61") (name "Net-(R121-Pad2)") (class "Default")
      (node (ref "R121") (pin "2") (pinfunction "2_2") (pintype "passive"))
      (node (ref "U31") (pin "3") (pinfunction "3_3") (pintype "passive"))
    )
    (net (code "62") (name "Net-(R122-Pad2)") (class "Default")
      (node (ref "R122") (pin "2") (pinfunction "2_2") (pintype "passive"))
      (node (ref "U32") (pin "3") (pinfunction "3_3") (pintype "passive"))
    )
    (net (code "63") (name "Net-(R123-Pad2)") (class "Default")
      (node (ref "R123") (pin "2") (pinfunction "2_2") (pintype "passive"))
      (node (ref "U33") (pin "3") (pinfunction "3_3") (pintype "passive"))
    )
    (net (code "64") (name "Net-(R124-Pad2)") (class "Default")
      (node (ref "R124") (pin "2") (pinfunction "2_2") (pintype "passive"))
      (node (ref "U34") (pin "3") (pinfunction "3_3") (pintype "passive"))
    )
    (net (code "65") (name "Net-(R125-Pad2)") (class "Default")
      (node (ref "R125") (pin "2") (pinfunction "2_2") (pintype "passive"))
      (node (ref "U35") (pin "3") (pinfunction "3_3") (pintype "passive"))
    )
    (net (code "66") (name "Net-(R126-Pad2)") (class "Default")
      (node (ref "R126") (pin "2") (pinfunction "2_2") (pintype "passive"))
      (node (ref "U36") (pin "3") (pinfunction "3_3") (pintype "passive"))
    )
    (net (code "67") (name "Net-(R127-Pad2)") (class "Default")
      (node (ref "R127") (pin "2") (pinfunction "2_2") (pintype "passive"))
      (node (ref "U37") (pin "3") (pinfunction "3_3") (pintype "passive"))
    )
    (net (code "68") (name "Net-(R128-Pad2)") (class "Default")
      (node (ref "R128") (pin "2") (pinfunction "2_2") (pintype "passive"))
      (node (ref "U38") (pin "3") (pinfunction "3_3") (pintype "passive"))
    )
    (net (code "69") (name "Net-(R129-Pad2)") (class "Default")
      (node (ref "R129") (pin "2") (pinfunction "2_2") (pintype "passive"))
      (node (ref "U39") (pin "3") (pinfunction "3_3") (pintype "passive"))
    )
    (net (code "70") (name "Net-(R130-Pad2)") (class "Default")
      (node (ref "R130") (pin "2") (pinfunction "2_2") (pintype "passive"))
      (node (ref "U40") (pin "3") (pinfunction "3_3") (pintype "passive"))
    )
    (net (code "71") (name "Net-(R131-Pad2)") (class "Default")
      (node (ref "R131") (pin "2") (pinfunction "2_2") (pintype "passive"))
      (node (ref "U41") (pin "3") (pinfunction "3_3") (pintype "passive"))
    )
    (net (code "72") (name "Net-(R132-Pad2)") (class "Default")
      (node (ref "R132") (pin "2") (pinfunction "2_2") (pintype "passive"))
      (node (ref "U42") (pin "3") (pinfunction "3_3") (pintype "passive"))
    )
    (net (code "73") (name "O1") (class "Default")
      (node (ref "R61") (pin "2") (pinfunction "2_2") (pintype "passive"))
    )
    (net (code "74") (name "O2") (class "Default")
      (node (ref "R62") (pin "2") (pinfunction "2_2") (pintype "passive"))
    )
    (net (code "75") (name "O3") (class "Default")
      (node (ref "R63") (pin "2") (pinfunction "2_2") (pintype "passive"))
    )
    (net (code "76") (name "O4") (class "Default")
      (node (ref "R64") (pin "2") (pinfunction "2_2") (pintype "passive"))
    )
    (net (code "77") (name "O5") (class "Default")
      (node (ref "R65") (pin "2") (pinfunction "2_2") (pintype "passive"))
    )
    (net (code "78") (name "O6") (class "Default")
      (node (ref "R66") (pin "2") (pinfunction "2_2") (pintype "passive"))
    )
    (net (code "79") (name "O7") (class "Default")
      (node (ref "R67") (pin "2") (pinfunction "2_2") (pintype "passive"))
    )
    (net (code "80") (name "O8") (class "Default")
      (node (ref "R68") (pin "2") (pinfunction "2_2") (pintype "passive"))
    )
    (net (code "81") (name "O9") (class "Default")
      (node (ref "R69") (pin "2") (pinfunction "2_2") (pintype "passive"))
    )
    (net (code "82") (name "O10") (class "Default")
      (node (ref "R70") (pin "2") (pinfunction "2_2") (pintype "passive"))
    )
    (net (code "83") (name "O11") (class "Default")
      (node (ref "R71") (pin "2") (pinfunction "2_2") (pintype "passive"))
    )
    (net (code "84") (name "O12") (class "Default")
      (node (ref "R72") (pin "2") (pinfunction "2_2") (pintype "passive"))
    )
    (net (code "85") (name "OUT_12") (class "Default")
      (node (ref "D72") (pin "1") (pinfunction "A_1") (pintype "passive"))
      (node (ref "Q32") (pin "3") (pinfunction "C_3") (pintype "passive"))
    )
    (net (code "86") (name "OUT_GND") (class "Default")
      (node (ref "J12") (pin "3") (pinfunction "3_3") (pintype "passive"))
      (node (ref "Q21") (pin "2") (pinfunction "E_2") (pintype "passive"))
      (node (ref "Q22") (pin "2") (pinfunction "E_2") (pintype "passive"))
      (node (ref "Q23") (pin "2") (pinfunction "E_2") (pintype "passive"))
      (node (ref "Q24") (pin "2") (pinfunction "E_2") (pintype "passive"))
      (node (ref "Q25") (pin "2") (pinfunction "E_2") (pintype "passive"))
      (node (ref "Q26") (pin "2") (pinfunction "E_2") (pintype "passive"))
      (node (ref "Q27") (pin "2") (pinfunction "E_2") (pintype "passive"))
      (node (ref "Q28") (pin "2") (pinfunction "E_2") (pintype "passive"))
      (node (ref "Q29") (pin "2") (pinfunction "E_2") (pintype "passive"))
      (node (ref "Q30") (pin "2") (pinfunction "E_2") (pintype "passive"))
      (node (ref "Q31") (pin "2") (pinfunction "E_2") (pintype "passive"))
      (node (ref "Q32") (pin "2") (pinfunction "E_2") (pintype "passive"))
      (node (ref "R101") (pin "1") (pinfunction "1_1") (pintype "passive"))
      (node (ref "R102") (pin "1") (pinfunction "1_1") (pintype "passive"))
      (node (ref "R103") (pin "1") (pinfunction "1_1") (pintype "passive"))
      (node (ref "R104") (pin "1") (pinfunction "1_1") (pintype "passive"))
      (node (ref "R105") (pin "1") (pinfunction "1_1") (pintype "passive"))
      (node (ref "R106") (pin "1") (pinfunction "1_1") (pintype "passive"))
      (node (ref "R107") (pin "1") (pinfunction "1_1") (pintype "passive"))
      (node (ref "R108") (pin "1") (pinfunction "1_1") (pintype "passive"))
      (node (ref "R109") (pin "1") (pinfunction "1_1") (pintype "passive"))
      (node (ref "R110") (pin "1") (pinfunction "1_1") (pintype "passive"))
      (node (ref "R111") (pin "1") (pinfunction "1_1") (pintype "passive"))
      (node (ref "R112") (pin "1") (pinfunction "1_1") (pintype "passive"))
    )
    (net (code "87") (name "VCC3v3") (class "Default")
      (node (ref "U31") (pin "1") (pinfunction "1_1") (pintype "passive"))
      (node (ref "U32") (pin "1") (pinfunction "1_1") (pintype "passive"))
      (node (ref "U33") (pin "1") (pinfunction "1_1") (pintype "passive"))
      (node (ref "U34") (pin "1") (pinfunction "1_1") (pintype "passive"))
      (node (ref "U35") (pin "1") (pinfunction "1_1") (pintype "passive"))
      (node (ref "U36") (pin "1") (pinfunction "1_1") (pintype "passive"))
      (node (ref "U37") (pin "1") (pinfunction "1_1") (pintype "passive"))
      (node (ref "U38") (pin "1") (pinfunction "1_1") (pintype "passive"))
      (node (ref "U39") (pin "1") (pinfunction "1_1") (pintype "passive"))
      (node (ref "U40") (pin "1") (pinfunction "1_1") (pintype "passive"))
      (node (ref "U41") (pin "1") (pinfunction "1_1") (pintype "passive"))
      (node (ref "U42") (pin "1") (pinfunction "1_1") (pintype "passive"))
    )
    (net (code "88") (name "VCC24") (class "Default")
      (node (ref "D61") (pin "2") (pinfunction "C_2") (pintype "passive"))
      (node (ref "D62") (pin "2") (pinfunction "C_2") (pintype "passive"))
      (node (ref "D63") (pin "2") (pinfunction "C_2") (pintype "passive"))
      (node (ref "D64") (pin "2") (pinfunction "C_2") (pintype "passive"))
      (node (ref "D65") (pin "2") (pinfunction "C_2") (pintype "passive"))
      (node (ref "D66") (pin "2") (pinfunction "C_2") (pintype "passive"))
      (node (ref "D67") (pin "2") (pinfunction "C_2") (pintype "passive"))
      (node (ref "D68") (pin "2") (pinfunction "C_2") (pintype "passive"))
      (node (ref "D69") (pin "2") (pinfunction "C_2") (pintype "passive"))
      (node (ref "D70") (pin "2") (pinfunction "C_2") (pintype "passive"))
      (node (ref "D71") (pin "2") (pinfunction "C_2") (pintype "passive"))
      (node (ref "D72") (pin "2") (pinfunction "C_2") (pintype "passive"))
      (node (ref "R81") (pin "2") (pinfunction "2_2") (pintype "passive"))
      (node (ref "R82") (pin "2") (pinfunction "2_2") (pintype "passive"))
      (node (ref "R83") (pin "2") (pinfunction "2_2") (pintype "passive"))
      (node (ref "R84") (pin "2") (pinfunction "2_2") (pintype "passive"))
      (node (ref "R85") (pin "2") (pinfunction "2_2") (pintype "passive"))
      (node (ref "R86") (pin "2") (pinfunction "2_2") (pintype "passive"))
      (node (ref "R87") (pin "2") (pinfunction "2_2") (pintype "passive"))
      (node (ref "R88") (pin "2") (pinfunction "2_2") (pintype "passive"))
      (node (ref "R89") (pin "2") (pinfunction "2_2") (pintype "passive"))
      (node (ref "R90") (pin "2") (pinfunction "2_2") (pintype "passive"))
      (node (ref "R91") (pin "2") (pinfunction "2_2") (pintype "passive"))
      (node (ref "R92") (pin "2") (pinfunction "2_2") (pintype "passive"))
    )
  )
)
